# SOM_IO3.net
KiCad netlist of a schematic drawn in Altium Designer
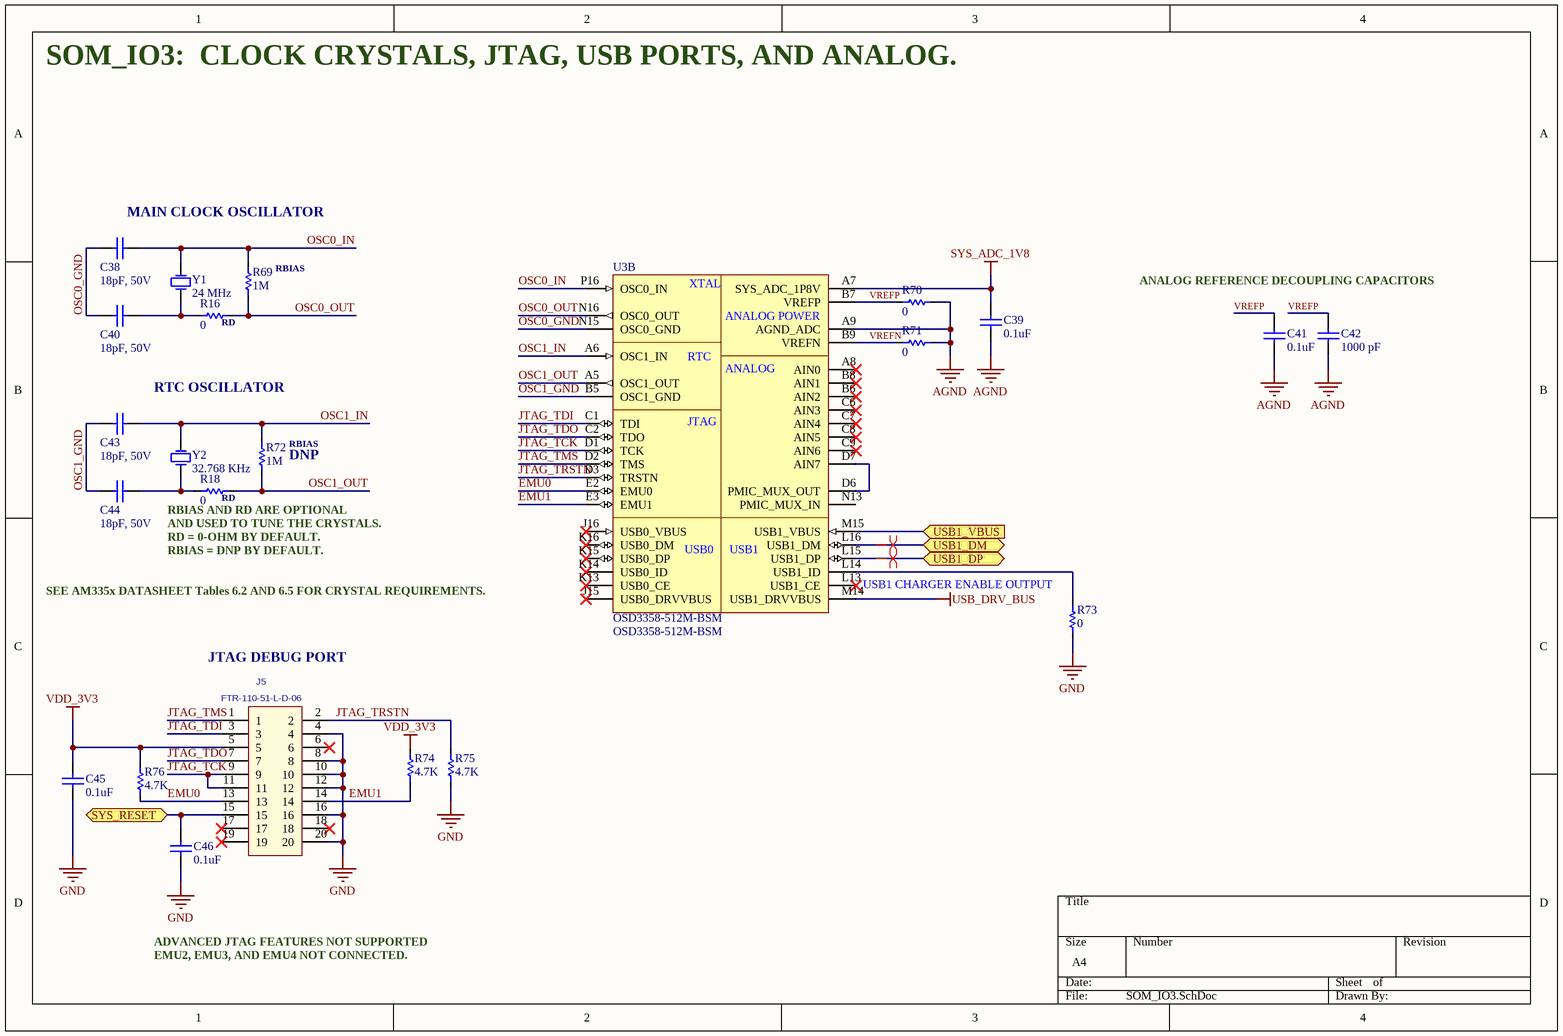
[diagram p0: SOM_IO3.SchDoc]

(export (version "E")
  (design (tool "Eeschema 10.0.6"))
  (components
    (comp (ref "C38")
      (value "18pF, 50V")
      (footprint "CAP_0603")
      (description "CAP CER 18PF 50V C0G/NP0 0603 +/- 0.5 PF")
      (fields (field (name "MANUFACTURER PART NO.") "C0603C180D5GACTU") (field (name "MANUFACTURER") "KEMET"))
      (libsource (lib "OSD335-X_Devboard") (part "C0603C180D5GACTU"))
    )
    (comp (ref "C39")
      (value "0.1uF")
      (footprint "CAP_0603")
      (description "CAP CER 0.1UF 16V X7R 0603")
      (fields (field (name "MANUFACTURER") "KEMET") (field (name "MANUFACTURER PART NO.") "C0603C104M4RACTU"))
      (libsource (lib "OSD335-X_Devboard") (part "C0603C104M4RACTU"))
    )
    (comp (ref "C40")
      (value "18pF, 50V")
      (footprint "CAP_0603")
      (description "CAP CER 18PF 50V C0G/NP0 0603 +/- 0.5 PF")
      (fields (field (name "MANUFACTURER PART NO.") "C0603C180D5GACTU") (field (name "MANUFACTURER") "KEMET"))
      (libsource (lib "OSD335-X_Devboard") (part "C0603C180D5GACTU"))
    )
    (comp (ref "C41")
      (value "0.1uF")
      (footprint "CAP_0603")
      (description "CAP CER 0.1UF 16V X7R 0603")
      (fields (field (name "MANUFACTURER") "KEMET") (field (name "MANUFACTURER PART NO.") "C0603C104M4RACTU"))
      (libsource (lib "OSD335-X_Devboard") (part "C0603C104M4RACTU"))
    )
    (comp (ref "C42")
      (value "1000 pF")
      (footprint "CAP_0603")
      (description "CAP CER 0603 1NF 16V X7R 5%")
      (fields
        (field (name "MANUFACTURER") "KEMET")
        (field (name "MANUFACTURER PART NO.") "C0603X102J4RECAUTO")
      )
      (libsource (lib "OSD335-X_Devboard") (part "C0603X102J4RECAUTO"))
    )
    (comp (ref "C43")
      (value "18pF, 50V")
      (footprint "CAP_0603")
      (description "CAP CER 18PF 50V C0G/NP0 0603 +/- 0.5 PF")
      (fields (field (name "MANUFACTURER PART NO.") "C0603C180D5GACTU") (field (name "MANUFACTURER") "KEMET"))
      (libsource (lib "OSD335-X_Devboard") (part "C0603C180D5GACTU"))
    )
    (comp (ref "C44")
      (value "18pF, 50V")
      (footprint "CAP_0603")
      (description "CAP CER 18PF 50V C0G/NP0 0603 +/- 0.5 PF")
      (fields (field (name "MANUFACTURER PART NO.") "C0603C180D5GACTU") (field (name "MANUFACTURER") "KEMET"))
      (libsource (lib "OSD335-X_Devboard") (part "C0603C180D5GACTU"))
    )
    (comp (ref "C45")
      (value "0.1uF")
      (footprint "CAP_0603")
      (description "CAP CER 0.1UF 16V X7R 0603")
      (fields (field (name "MANUFACTURER") "KEMET") (field (name "MANUFACTURER PART NO.") "C0603C104M4RACTU"))
      (libsource (lib "OSD335-X_Devboard") (part "C0603C104M4RACTU"))
    )
    (comp (ref "C46")
      (value "0.1uF")
      (footprint "CAP_0603")
      (description "CAP CER 0.1UF 16V X7R 0603")
      (fields (field (name "MANUFACTURER") "KEMET") (field (name "MANUFACTURER PART NO.") "C0603C104M4RACTU"))
      (libsource (lib "OSD335-X_Devboard") (part "C0603C104M4RACTU"))
    )
    (comp (ref "J5")
      (value "FTR-110-51-L-D-06")
      (footprint "HEADER_2X10_1.7MM")
      (description "CONN HEADER SMD 20POS 1.27MM")
      (fields (field (name "MANUFACTURER") "SAMTEC"))
      (libsource (lib "OSD335-X_Devboard") (part "FTR-110-51-L-D-06"))
    )
    (comp (ref "R16")
      (value "0")
      (footprint "RES_0603")
      (description "RES SMD 0 OHM JUMPER 1/10W 0603")
      (fields (field (name "MANUFACTURER") "Yageo") (field (name "MANUFACTURER PART NO.") "RC0603JR-070RL"))
      (libsource (lib "OSD335-X_Devboard") (part "RC0603JR-070RL"))
    )
    (comp (ref "R18")
      (value "0")
      (footprint "RES_0603")
      (description "RES SMD 0 OHM JUMPER 1/10W 0603")
      (fields (field (name "MANUFACTURER") "Yageo") (field (name "MANUFACTURER PART NO.") "RC0603JR-070RL"))
      (libsource (lib "OSD335-X_Devboard") (part "RC0603JR-070RL"))
    )
    (comp (ref "R69")
      (value "1M")
      (footprint "RES_0603")
      (description "RES SMD 1M OHM 5% 1/10W 0603")
      (fields (field (name "TOLERANCE") "5%") (field (name "MANUFACTURER") "Yageo"))
      (libsource (lib "OSD335-X_Devboard") (part "RC0603JR-071ML"))
    )
    (comp (ref "R70")
      (value "0")
      (footprint "RES_0603")
      (description "RES SMD 0 OHM JUMPER 1/10W 0603")
      (fields (field (name "MANUFACTURER") "Yageo") (field (name "MANUFACTURER PART NO.") "RC0603JR-070RL"))
      (libsource (lib "OSD335-X_Devboard") (part "RC0603JR-070RL"))
    )
    (comp (ref "R71")
      (value "0")
      (footprint "RES_0603")
      (description "RES SMD 0 OHM JUMPER 1/10W 0603")
      (fields (field (name "MANUFACTURER") "Yageo") (field (name "MANUFACTURER PART NO.") "RC0603JR-070RL"))
      (libsource (lib "OSD335-X_Devboard") (part "RC0603JR-070RL"))
    )
    (comp (ref "R72")
      (value "1M")
      (footprint "RES_0603")
      (description "RES SMD 1M OHM 5% 1/10W 0603")
      (fields (field (name "TOLERANCE") "5%") (field (name "MANUFACTURER") "Yageo"))
      (libsource (lib "OSD335-X_Devboard") (part "RC0603JR-071ML"))
    )
    (comp (ref "R73")
      (value "0")
      (footprint "RES_0603")
      (description "RES SMD 0 OHM JUMPER 1/10W 0603")
      (fields (field (name "MANUFACTURER") "Yageo") (field (name "MANUFACTURER PART NO.") "RC0603JR-070RL"))
      (libsource (lib "OSD335-X_Devboard") (part "RC0603JR-070RL"))
    )
    (comp (ref "R74")
      (value "4.7K")
      (footprint "RES_0603")
      (description "RES SMD 4.7K OHM 5% 1/10W 0603")
      (fields (field (name "TOLERANCE") "5%") (field (name "MANUFACTURER") "Yageo"))
      (libsource (lib "OSD335-X_Devboard") (part "RC0603JR-074K7L"))
    )
    (comp (ref "R75")
      (value "4.7K")
      (footprint "RES_0603")
      (description "RES SMD 4.7K OHM 5% 1/10W 0603")
      (fields (field (name "TOLERANCE") "5%") (field (name "MANUFACTURER") "Yageo"))
      (libsource (lib "OSD335-X_Devboard") (part "RC0603JR-074K7L"))
    )
    (comp (ref "R76")
      (value "4.7K")
      (footprint "RES_0603")
      (description "RES SMD 4.7K OHM 5% 1/10W 0603")
      (fields (field (name "TOLERANCE") "5%") (field (name "MANUFACTURER") "Yageo"))
      (libsource (lib "OSD335-X_Devboard") (part "RC0603JR-074K7L"))
    )
    (comp (ref "U3")
      (value "OSD3358-512M-BSM")
      (footprint "BGA256C127P16X16_2100X2100X308")
      (description "OSD3358-512M-BSM , 256-FBGA, 21mmx21mmx3mm")
      (fields (field (name "MANUFACTURER") "Octavo Systems") (field (name "PARTNUMBER") "OSD3358-512M-BSM"))
      (libsource (lib "OSD335-X_Devboard") (part "SOM-OSD3358-512M-BSM"))
    )
    (comp (ref "Y1")
      (value "24 MHz")
      (footprint "7A-24MHz")
      (description "CRYSTAL 24.0000MHZ 18PF SMD")
      (fields
        (field (name "MANUFACTURER") "TXC CORPORATION")
        (field (name "MANUFACTURER PART NO.") "7A-24.000MAAJ-T")
      )
      (libsource (lib "OSD335-X_Devboard") (part "7A-24.000MAAJ-T"))
    )
    (comp (ref "Y2")
      (value "32.768 KHz")
      (footprint "ABS07")
      (description "CRYSTAL 32.7680KHZ 12.5PF SMD")
      (fields
        (field (name "MANUFACTURER") "Abracon LLC")
        (field (name "MANUFACTURER PART NO.") "ABS07-32.768KHZ-T")
      )
      (libsource (lib "OSD335-X_Devboard") (part "ABS07-32.768KHZ-T"))
    )
  )
  (nets
    (net (code "1") (name "/EMU0") (class "Default")
      (node (ref "J5") (pin "13") (pinfunction "13_13") (pintype "passive"))
      (node (ref "R76") (pin "1") (pinfunction "1_1") (pintype "passive"))
      (node (ref "U3") (pin "E2") (pinfunction "EMU0_E2") (pintype "bidirectional"))
    )
    (net (code "2") (name "/EMU1") (class "Default")
      (node (ref "J5") (pin "14") (pinfunction "14_14") (pintype "passive"))
      (node (ref "R74") (pin "1") (pinfunction "1_1") (pintype "passive"))
      (node (ref "U3") (pin "E3") (pinfunction "EMU1_E3") (pintype "bidirectional"))
    )
    (net (code "3") (name "/JTAG_TCK") (class "Default")
      (node (ref "J5") (pin "11") (pinfunction "11_11") (pintype "passive"))
      (node (ref "J5") (pin "9") (pinfunction "9_9") (pintype "passive"))
      (node (ref "U3") (pin "D1") (pinfunction "TCK_D1") (pintype "bidirectional"))
    )
    (net (code "4") (name "/JTAG_TDI") (class "Default")
      (node (ref "J5") (pin "3") (pinfunction "3_3") (pintype "passive"))
      (node (ref "U3") (pin "C1") (pinfunction "TDI_C1") (pintype "bidirectional"))
    )
    (net (code "5") (name "/JTAG_TDO") (class "Default")
      (node (ref "J5") (pin "7") (pinfunction "7_7") (pintype "passive"))
      (node (ref "U3") (pin "C2") (pinfunction "TDO_C2") (pintype "bidirectional"))
    )
    (net (code "6") (name "/JTAG_TMS") (class "Default")
      (node (ref "J5") (pin "1") (pinfunction "1_1") (pintype "passive"))
      (node (ref "U3") (pin "D2") (pinfunction "TMS_D2") (pintype "bidirectional"))
    )
    (net (code "7") (name "/JTAG_TRSTN") (class "Default")
      (node (ref "J5") (pin "2") (pinfunction "2_2") (pintype "passive"))
      (node (ref "R75") (pin "2") (pinfunction "2_2") (pintype "passive"))
      (node (ref "U3") (pin "D3") (pinfunction "TRSTN_D3") (pintype "bidirectional"))
    )
    (net (code "8") (name "/OSC0_GND") (class "Default")
      (node (ref "C38") (pin "2") (pinfunction "P_2") (pintype "passive"))
      (node (ref "C40") (pin "2") (pinfunction "P_2") (pintype "passive"))
      (node (ref "U3") (pin "N15") (pinfunction "OSC0_GND_N15") (pintype "power_in"))
    )
    (net (code "9") (name "/OSC0_IN") (class "Default")
      (node (ref "C38") (pin "1") (pinfunction "N_1") (pintype "passive"))
      (node (ref "R69") (pin "2") (pinfunction "2_2") (pintype "passive"))
      (node (ref "U3") (pin "P16") (pinfunction "OSC0_IN_P16") (pintype "input"))
      (node (ref "Y1") (pin "2") (pinfunction "OSC2_2") (pintype "passive"))
    )
    (net (code "10") (name "/OSC0_OUT") (class "Default")
      (node (ref "R16") (pin "2") (pinfunction "2_2") (pintype "passive"))
      (node (ref "R69") (pin "1") (pinfunction "1_1") (pintype "passive"))
      (node (ref "U3") (pin "N16") (pinfunction "OSC0_OUT_N16") (pintype "output"))
    )
    (net (code "11") (name "/OSC1_GND") (class "Default")
      (node (ref "C43") (pin "2") (pinfunction "P_2") (pintype "passive"))
      (node (ref "C44") (pin "2") (pinfunction "P_2") (pintype "passive"))
      (node (ref "U3") (pin "B5") (pinfunction "OSC1_GND_B5") (pintype "power_in"))
    )
    (net (code "12") (name "/OSC1_IN") (class "Default")
      (node (ref "C43") (pin "1") (pinfunction "N_1") (pintype "passive"))
      (node (ref "R72") (pin "2") (pinfunction "2_2") (pintype "passive"))
      (node (ref "U3") (pin "A6") (pinfunction "OSC1_IN_A6") (pintype "input"))
      (node (ref "Y2") (pin "2") (pinfunction "OSC2_2") (pintype "passive"))
    )
    (net (code "13") (name "/OSC1_OUT") (class "Default")
      (node (ref "R18") (pin "2") (pinfunction "2_2") (pintype "passive"))
      (node (ref "R72") (pin "1") (pinfunction "1_1") (pintype "passive"))
      (node (ref "U3") (pin "A5") (pinfunction "OSC1_OUT_A5") (pintype "output"))
    )
    (net (code "14") (name "/SYS_RESET") (class "Default")
      (node (ref "C46") (pin "2") (pinfunction "2_2") (pintype "passive"))
      (node (ref "J5") (pin "15") (pinfunction "15_15") (pintype "passive"))
    )
    (net (code "15") (name "/USB1_DM") (class "Default")
      (node (ref "U3") (pin "L16") (pinfunction "USB1_DM_L16") (pintype "bidirectional"))
    )
    (net (code "16") (name "/USB1_DP") (class "Default")
      (node (ref "U3") (pin "L15") (pinfunction "USB1_DP_L15") (pintype "bidirectional"))
    )
    (net (code "17") (name "/USB1_VBUS") (class "Default")
      (node (ref "U3") (pin "M15") (pinfunction "USB1_VBUS_M15") (pintype "input"))
    )
    (net (code "18") (name "/VREFN") (class "Default")
      (node (ref "R71") (pin "1") (pinfunction "1_1") (pintype "passive"))
      (node (ref "U3") (pin "B9") (pinfunction "VREFN_B9") (pintype "power_in"))
    )
    (net (code "19") (name "/VREFP") (class "Default")
      (node (ref "C41") (pin "2") (pinfunction "2_2") (pintype "passive"))
      (node (ref "C42") (pin "2") (pinfunction "2_2") (pintype "passive"))
      (node (ref "R70") (pin "1") (pinfunction "1_1") (pintype "passive"))
      (node (ref "U3") (pin "B7") (pinfunction "VREFP_B7") (pintype "power_in"))
    )
    (net (code "20") (name "AGND") (class "Default")
      (node (ref "C39") (pin "1") (pinfunction "1_1") (pintype "passive"))
      (node (ref "C41") (pin "1") (pinfunction "1_1") (pintype "passive"))
      (node (ref "C42") (pin "1") (pinfunction "1_1") (pintype "passive"))
      (node (ref "R70") (pin "2") (pinfunction "2_2") (pintype "passive"))
      (node (ref "R71") (pin "2") (pinfunction "2_2") (pintype "passive"))
      (node (ref "U3") (pin "A9") (pinfunction "AGND_ADC_A9") (pintype "power_in"))
    )
    (net (code "21") (name "GND") (class "Default")
      (node (ref "C45") (pin "1") (pinfunction "1_1") (pintype "passive"))
      (node (ref "C46") (pin "1") (pinfunction "1_1") (pintype "passive"))
      (node (ref "J5") (pin "10") (pinfunction "10_10") (pintype "passive"))
      (node (ref "J5") (pin "12") (pinfunction "12_12") (pintype "passive"))
      (node (ref "J5") (pin "16") (pinfunction "16_16") (pintype "passive"))
      (node (ref "J5") (pin "20") (pinfunction "20_20") (pintype "passive"))
      (node (ref "J5") (pin "4") (pinfunction "4_4") (pintype "passive"))
      (node (ref "J5") (pin "8") (pinfunction "8_8") (pintype "passive"))
      (node (ref "R73") (pin "2") (pinfunction "2_2") (pintype "passive"))
      (node (ref "R75") (pin "1") (pinfunction "1_1") (pintype "passive"))
    )
    (net (code "22") (name "Net-(C40-N)") (class "Default")
      (node (ref "C40") (pin "1") (pinfunction "N_1") (pintype "passive"))
      (node (ref "R16") (pin "1") (pinfunction "1_1") (pintype "passive"))
      (node (ref "Y1") (pin "1") (pinfunction "OSC1_1") (pintype "passive"))
    )
    (net (code "23") (name "Net-(C44-N)") (class "Default")
      (node (ref "C44") (pin "1") (pinfunction "N_1") (pintype "passive"))
      (node (ref "R18") (pin "1") (pinfunction "1_1") (pintype "passive"))
      (node (ref "Y2") (pin "1") (pinfunction "OSC1_1") (pintype "passive"))
    )
    (net (code "24") (name "Net-(U3B-AIN7)") (class "Default")
      (node (ref "U3") (pin "D6") (pinfunction "PMIC_MUX_OUT_D6") (pintype "passive"))
      (node (ref "U3") (pin "D7") (pinfunction "AIN7_D7") (pintype "passive"))
    )
    (net (code "25") (name "Net-(U3B-USB1_ID)") (class "Default")
      (node (ref "R73") (pin "1") (pinfunction "1_1") (pintype "passive"))
      (node (ref "U3") (pin "L14") (pinfunction "USB1_ID_L14") (pintype "passive"))
    )
    (net (code "26") (name "SYS_ADC_1V8") (class "Default")
      (node (ref "C39") (pin "2") (pinfunction "2_2") (pintype "passive"))
      (node (ref "U3") (pin "A7") (pinfunction "SYS_ADC_1P8V_A7") (pintype "power_in"))
    )
    (net (code "27") (name "USB_DRV_BUS") (class "Default")
      (node (ref "U3") (pin "M14") (pinfunction "USB1_DRVVBUS_M14") (pintype "power_in"))
    )
    (net (code "28") (name "VDD_3V3") (class "Default")
      (node (ref "C45") (pin "2") (pinfunction "2_2") (pintype "passive"))
      (node (ref "J5") (pin "5") (pinfunction "5_5") (pintype "passive"))
      (node (ref "R74") (pin "2") (pinfunction "2_2") (pintype "passive"))
      (node (ref "R76") (pin "2") (pinfunction "2_2") (pintype "passive"))
    )
    (net (code "29") (name "unconnected-(J5-Pad6)") (class "Default")
      (node (ref "J5") (pin "6") (pinfunction "6_6") (pintype "passive+no_connect"))
    )
    (net (code "30") (name "unconnected-(J5-Pad17)") (class "Default")
      (node (ref "J5") (pin "17") (pinfunction "17_17") (pintype "passive+no_connect"))
    )
    (net (code "31") (name "unconnected-(J5-Pad18)") (class "Default")
      (node (ref "J5") (pin "18") (pinfunction "18_18") (pintype "passive+no_connect"))
    )
    (net (code "32") (name "unconnected-(J5-Pad19)") (class "Default")
      (node (ref "J5") (pin "19") (pinfunction "19_19") (pintype "passive+no_connect"))
    )
    (net (code "33") (name "unconnected-(U3B-AIN0-PadA8)") (class "Default")
      (node (ref "U3") (pin "A8") (pinfunction "AIN0_A8") (pintype "passive+no_connect"))
    )
    (net (code "34") (name "unconnected-(U3B-AIN1-PadB8)") (class "Default")
      (node (ref "U3") (pin "B8") (pinfunction "AIN1_B8") (pintype "passive+no_connect"))
    )
    (net (code "35") (name "unconnected-(U3B-AIN2-PadB6)") (class "Default")
      (node (ref "U3") (pin "B6") (pinfunction "AIN2_B6") (pintype "passive+no_connect"))
    )
    (net (code "36") (name "unconnected-(U3B-AIN3-PadC6)") (class "Default")
      (node (ref "U3") (pin "C6") (pinfunction "AIN3_C6") (pintype "passive+no_connect"))
    )
    (net (code "37") (name "unconnected-(U3B-AIN4-PadC7)") (class "Default")
      (node (ref "U3") (pin "C7") (pinfunction "AIN4_C7") (pintype "passive+no_connect"))
    )
    (net (code "38") (name "unconnected-(U3B-AIN5-PadC8)") (class "Default")
      (node (ref "U3") (pin "C8") (pinfunction "AIN5_C8") (pintype "passive+no_connect"))
    )
    (net (code "39") (name "unconnected-(U3B-AIN6-PadC9)") (class "Default")
      (node (ref "U3") (pin "C9") (pinfunction "AIN6_C9") (pintype "passive+no_connect"))
    )
    (net (code "40") (name "unconnected-(U3B-PMIC_MUX_IN-PadN13)") (class "Default")
      (node (ref "U3") (pin "N13") (pinfunction "PMIC_MUX_IN_N13") (pintype "passive"))
    )
    (net (code "41") (name "unconnected-(U3B-USB0_CE-PadK13)") (class "Default")
      (node (ref "U3") (pin "K13") (pinfunction "USB0_CE_K13") (pintype "power_in+no_connect"))
    )
    (net (code "42") (name "unconnected-(U3B-USB0_DM-PadK16)") (class "Default")
      (node (ref "U3") (pin "K16") (pinfunction "USB0_DM_K16") (pintype "bidirectional+no_connect"))
    )
    (net (code "43") (name "unconnected-(U3B-USB0_DP-PadK15)") (class "Default")
      (node (ref "U3") (pin "K15") (pinfunction "USB0_DP_K15") (pintype "bidirectional+no_connect"))
    )
    (net (code "44") (name "unconnected-(U3B-USB0_DRVVBUS-PadJ15)") (class "Default")
      (node (ref "U3") (pin "J15") (pinfunction "USB0_DRVVBUS_J15") (pintype "power_in+no_connect"))
    )
    (net (code "45") (name "unconnected-(U3B-USB0_ID-PadK14)") (class "Default")
      (node (ref "U3") (pin "K14") (pinfunction "USB0_ID_K14") (pintype "passive+no_connect"))
    )
    (net (code "46") (name "unconnected-(U3B-USB0_VBUS-PadJ16)") (class "Default")
      (node (ref "U3") (pin "J16") (pinfunction "USB0_VBUS_J16") (pintype "input+no_connect"))
    )
    (net (code "47") (name "unconnected-(U3B-USB1_CE-PadL13)") (class "Default")
      (node (ref "U3") (pin "L13") (pinfunction "USB1_CE_L13") (pintype "power_in+no_connect"))
    )
  )
)
